# Power_Supply.net
KiCad netlist of a schematic drawn in Altium Designer
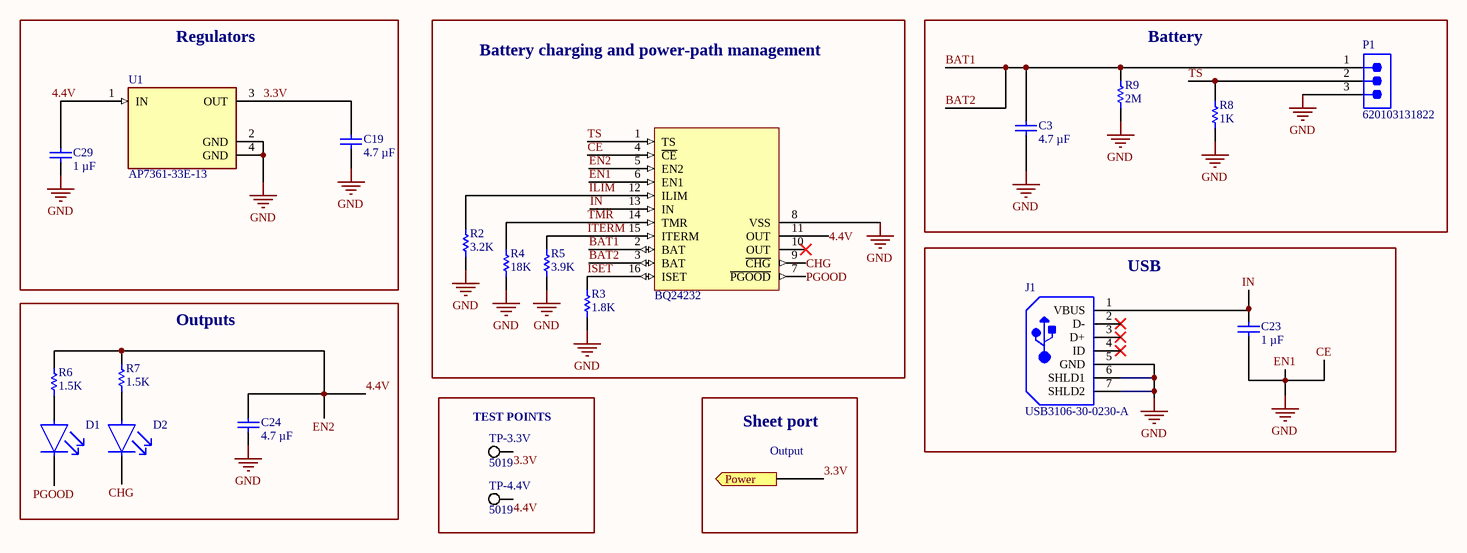
[diagram p0: Power_Supply.SchDoc]

(export (version "E")
  (design (tool "Eeschema 10.0.6"))
  (components
    (comp (ref "BQ24232") (value "BQ24232") (footprint "VQFN") (libsource (lib "FEEL2324") (part "BQ24232")))
    (comp (ref "C3")
      (value "4.7 µF")
      (footprint "CAPC1005X70X10ML20T00")
      (fields
        (field (name "MANUFACTURER") "AVX Interconnect / Elco")
        (field (name "PART NUMBER") "TACK475M003QTA")
      )
      (libsource (lib "Altium Content Vault") (part "CAP"))
    )
    (comp (ref "C19")
      (value "4.7 µF")
      (footprint "CAPC1005X70X10ML20T00")
      (fields
        (field (name "MANUFACTURER") "AVX Interconnect / Elco")
        (field (name "PART NUMBER") "TACK475M003QTA")
      )
      (libsource (lib "Altium Content Vault") (part "CAP"))
    )
    (comp (ref "C23")
      (value "1 µF")
      (footprint "CAPC2013X135X45LL10T25")
      (fields (field (name "MANUFACTURER") "Murata") (field (name "PART NUMBER") "GRM21BR71H105KA12L"))
      (libsource (lib "Altium Content Vault") (part "CAP"))
    )
    (comp (ref "C24")
      (value "4.7 µF")
      (footprint "CAPC1005X70X10ML20T00")
      (fields
        (field (name "MANUFACTURER") "AVX Interconnect / Elco")
        (field (name "PART NUMBER") "TACK475M003QTA")
      )
      (libsource (lib "Altium Content Vault") (part "CAP"))
    )
    (comp (ref "C29")
      (value "1 µF")
      (footprint "CAPC2013X135X45LL10T25")
      (fields (field (name "MANUFACTURER") "Murata") (field (name "PART NUMBER") "GRM21BR71H105KA12L"))
      (libsource (lib "Altium Content Vault") (part "CAP"))
    )
    (comp (ref "D1")
      (value "~")
      (footprint "FP-LTST-C190GKT-MFG")
      (description "LED GREEN CLEAR CHIP SMD")
      (fields (field (name "VOLTAGE") "2V"))
      (libsource (lib "Altium Content Vault") (part "8706943c75ba83719d021d2fdc84c58"))
    )
    (comp (ref "D2")
      (value "~")
      (footprint "FP-LTST-C190GKT-MFG")
      (description "LED GREEN CLEAR CHIP SMD")
      (fields (field (name "VOLTAGE") "2V"))
      (libsource (lib "Altium Content Vault") (part "8706943c75ba83719d021d2fdc84c58"))
    )
    (comp (ref "J1")
      (value "USB3106-30-0230-A")
      (footprint "GCT-USB3106-30-0230-A_V")
      (fields (field (name "MANUFACTURER") "Global Connector Technology"))
      (libsource (lib "Components - 16.11.23 - 09.59") (part "CMP-2000-07367-1"))
    )
    (comp (ref "P1")
      (value "620103131822")
      (footprint "620103131822")
      (libsource (lib "Altium Content Vault") (part "Header_Male_1R_03P"))
    )
    (comp (ref "R2")
      (value "3.2K")
      (footprint "RESC3216X70X50NL05T20")
      (fields (field (name "MANUFACTURER") "Panasonic") (field (name "PART NUMBER") "ERJ-8GEY0R00V"))
      (libsource (lib "Altium Content Vault") (part "RES"))
    )
    (comp (ref "R3")
      (value "1.8K")
      (footprint "RESC3216X70X50NL05T20")
      (fields (field (name "MANUFACTURER") "Panasonic") (field (name "PART NUMBER") "ERJ-8GEY0R00V"))
      (libsource (lib "Altium Content Vault") (part "RES"))
    )
    (comp (ref "R4")
      (value "18K")
      (footprint "RESC3216X70X50NL05T20")
      (fields (field (name "MANUFACTURER") "Panasonic") (field (name "PART NUMBER") "ERJ-8GEY0R00V"))
      (libsource (lib "Altium Content Vault") (part "RES"))
    )
    (comp (ref "R5")
      (value "3.9K")
      (footprint "RESC3216X70X50NL05T20")
      (fields (field (name "MANUFACTURER") "Panasonic") (field (name "PART NUMBER") "ERJ-8GEY0R00V"))
      (libsource (lib "Altium Content Vault") (part "RES"))
    )
    (comp (ref "R6")
      (value "1.5K")
      (footprint "RESC3216X70X50NL05T20")
      (fields (field (name "MANUFACTURER") "Panasonic") (field (name "PART NUMBER") "ERJ-8GEY0R00V"))
      (libsource (lib "Altium Content Vault") (part "RES"))
    )
    (comp (ref "R7")
      (value "1.5K")
      (footprint "RESC3216X70X50NL05T20")
      (fields (field (name "MANUFACTURER") "Panasonic") (field (name "PART NUMBER") "ERJ-8GEY0R00V"))
      (libsource (lib "Altium Content Vault") (part "RES"))
    )
    (comp (ref "R8")
      (value "1K")
      (footprint "RESC3216X70X50NL05T20")
      (fields (field (name "MANUFACTURER") "Panasonic") (field (name "PART NUMBER") "ERJ-8GEY0R00V"))
      (libsource (lib "Altium Content Vault") (part "RES"))
    )
    (comp (ref "R9")
      (value "2M")
      (footprint "RESC3216X70X50NL05T20")
      (fields (field (name "MANUFACTURER") "Panasonic") (field (name "PART NUMBER") "ERJ-8GEY0R00V"))
      (libsource (lib "Altium Content Vault") (part "RES"))
    )
    (comp (ref "TP-3.3V")
      (value "5019")
      (footprint "KSTN-5019_V")
      (description "Test Point, 1 Position SMD, RoHS, Tape and Reel")
      (libsource (lib "Altium Content Vault") (part "TESTPOINT_WHITE"))
    )
    (comp (ref "TP-4.4V")
      (value "5019")
      (footprint "KSTN-5019_V")
      (description "Test Point, 1 Position SMD, RoHS, Tape and Reel")
      (libsource (lib "Altium Content Vault") (part "TESTPOINT_WHITE"))
    )
    (comp (ref "U1")
      (value "AP7361-33E-13")
      (footprint "FP-SOT223-IPC_C")
      (description "IC REG LINEAR 3.3V 1A SOT223")
      (libsource (lib "Altium Content Vault") (part "9ab15734ea0ee80ef7f5ab97f35b097"))
    )
  )
  (nets
    (net (code "1") (name "/3.3V") (class "Default")
      (node (ref "C19") (pin "2") (pinfunction "2_2") (pintype "passive"))
      (node (ref "TP-3.3V") (pin "1") (pinfunction "1_1") (pintype "passive"))
      (node (ref "U1") (pin "3") (pinfunction "OUT_3") (pintype "passive"))
    )
    (net (code "2") (name "/4.4V") (class "Default")
      (node (ref "BQ24232") (pin "11") (pinfunction "OUT_11") (pintype "power_in"))
      (node (ref "BQ24232") (pin "5") (pinfunction "EN2_5") (pintype "input"))
      (node (ref "C24") (pin "2") (pinfunction "2_2") (pintype "passive"))
      (node (ref "C29") (pin "2") (pinfunction "2_2") (pintype "passive"))
      (node (ref "R6") (pin "2") (pinfunction "2_2") (pintype "passive"))
      (node (ref "R7") (pin "2") (pinfunction "2_2") (pintype "passive"))
      (node (ref "TP-4.4V") (pin "1") (pinfunction "1_1") (pintype "passive"))
      (node (ref "U1") (pin "1") (pinfunction "IN_1") (pintype "input"))
    )
    (net (code "3") (name "/BAT1") (class "Default")
      (node (ref "BQ24232") (pin "2") (pinfunction "BAT_2") (pintype "bidirectional"))
      (node (ref "BQ24232") (pin "3") (pinfunction "BAT_3") (pintype "bidirectional"))
      (node (ref "C3") (pin "2") (pinfunction "2_2") (pintype "passive"))
      (node (ref "P1") (pin "1") (pinfunction "1_1") (pintype "passive"))
      (node (ref "R9") (pin "2") (pinfunction "2_2") (pintype "passive"))
    )
    (net (code "4") (name "/CHG") (class "Default")
      (node (ref "BQ24232") (pin "9") (pinfunction "~{CHG}_9") (pintype "output"))
      (node (ref "D2") (pin "1") (pinfunction "C_1") (pintype "passive"))
    )
    (net (code "5") (name "/ILIM") (class "Default")
      (node (ref "BQ24232") (pin "12") (pinfunction "ILIM_12") (pintype "input"))
      (node (ref "R2") (pin "2") (pinfunction "2_2") (pintype "passive"))
    )
    (net (code "6") (name "/IN") (class "Default")
      (node (ref "BQ24232") (pin "13") (pinfunction "IN_13") (pintype "input"))
      (node (ref "C23") (pin "2") (pinfunction "2_2") (pintype "passive"))
      (node (ref "J1") (pin "1") (pinfunction "VBUS_1") (pintype "passive"))
    )
    (net (code "7") (name "/ISET") (class "Default")
      (node (ref "BQ24232") (pin "16") (pinfunction "ISET_16") (pintype "bidirectional"))
      (node (ref "R3") (pin "2") (pinfunction "2_2") (pintype "passive"))
    )
    (net (code "8") (name "/ITERM") (class "Default")
      (node (ref "BQ24232") (pin "15") (pinfunction "ITERM_15") (pintype "input"))
      (node (ref "R5") (pin "1") (pinfunction "1_1") (pintype "passive"))
    )
    (net (code "9") (name "/PGOOD") (class "Default")
      (node (ref "BQ24232") (pin "7") (pinfunction "~{PGOOD}_7") (pintype "output"))
      (node (ref "D1") (pin "1") (pinfunction "C_1") (pintype "passive"))
    )
    (net (code "10") (name "/TMR") (class "Default")
      (node (ref "BQ24232") (pin "14") (pinfunction "TMR_14") (pintype "input"))
      (node (ref "R4") (pin "1") (pinfunction "1_1") (pintype "passive"))
    )
    (net (code "11") (name "/TS") (class "Default")
      (node (ref "BQ24232") (pin "1") (pinfunction "TS_1") (pintype "input"))
      (node (ref "P1") (pin "2") (pinfunction "2_2") (pintype "passive"))
      (node (ref "R8") (pin "2") (pinfunction "2_2") (pintype "passive"))
    )
    (net (code "12") (name "GND") (class "Default")
      (node (ref "BQ24232") (pin "4") (pinfunction "~{CE}_4") (pintype "input"))
      (node (ref "BQ24232") (pin "6") (pinfunction "EN1_6") (pintype "input"))
      (node (ref "BQ24232") (pin "8") (pinfunction "VSS_8") (pintype "power_in"))
      (node (ref "C19") (pin "1") (pinfunction "1_1") (pintype "passive"))
      (node (ref "C23") (pin "1") (pinfunction "1_1") (pintype "passive"))
      (node (ref "C24") (pin "1") (pinfunction "1_1") (pintype "passive"))
      (node (ref "C29") (pin "1") (pinfunction "1_1") (pintype "passive"))
      (node (ref "C3") (pin "1") (pinfunction "1_1") (pintype "passive"))
      (node (ref "J1") (pin "5") (pinfunction "GND_5") (pintype "passive"))
      (node (ref "J1") (pin "6") (pinfunction "SHLD1_6") (pintype "passive"))
      (node (ref "J1") (pin "7") (pinfunction "SHLD2_7") (pintype "passive"))
      (node (ref "P1") (pin "3") (pinfunction "3_3") (pintype "passive"))
      (node (ref "R2") (pin "1") (pinfunction "1_1") (pintype "passive"))
      (node (ref "R3") (pin "1") (pinfunction "1_1") (pintype "passive"))
      (node (ref "R4") (pin "2") (pinfunction "2_2") (pintype "passive"))
      (node (ref "R5") (pin "2") (pinfunction "2_2") (pintype "passive"))
      (node (ref "R8") (pin "1") (pinfunction "1_1") (pintype "passive"))
      (node (ref "R9") (pin "1") (pinfunction "1_1") (pintype "passive"))
      (node (ref "U1") (pin "2") (pinfunction "GND_2") (pintype "power_in"))
      (node (ref "U1") (pin "4") (pinfunction "GND_4") (pintype "power_in"))
    )
    (net (code "13") (name "unconnected-(BQ24232-OUT-Pad10)") (class "Default")
      (node (ref "BQ24232") (pin "10") (pinfunction "OUT_10") (pintype "power_in+no_connect"))
    )
    (net (code "14") (name "unconnected-(D1-A-Pad2)") (class "Default")
      (node (ref "D1") (pin "2") (pinfunction "A_2") (pintype "passive"))
    )
    (net (code "15") (name "unconnected-(D2-A-Pad2)") (class "Default")
      (node (ref "D2") (pin "2") (pinfunction "A_2") (pintype "passive"))
    )
    (net (code "16") (name "unconnected-(J1-D+-Pad3)") (class "Default")
      (node (ref "J1") (pin "3") (pinfunction "D+_3") (pintype "passive+no_connect"))
    )
    (net (code "17") (name "unconnected-(J1-D--Pad2)") (class "Default")
      (node (ref "J1") (pin "2") (pinfunction "D-_2") (pintype "passive+no_connect"))
    )
    (net (code "18") (name "unconnected-(J1-ID-Pad4)") (class "Default")
      (node (ref "J1") (pin "4") (pinfunction "ID_4") (pintype "passive+no_connect"))
    )
    (net (code "19") (name "unconnected-(R6-Pad1)") (class "Default")
      (node (ref "R6") (pin "1") (pinfunction "1_1") (pintype "passive"))
    )
    (net (code "20") (name "unconnected-(R7-Pad1)") (class "Default")
      (node (ref "R7") (pin "1") (pinfunction "1_1") (pintype "passive"))
    )
  )
)
